# S4M13.net
KiCad netlist of a schematic drawn in EAGLE
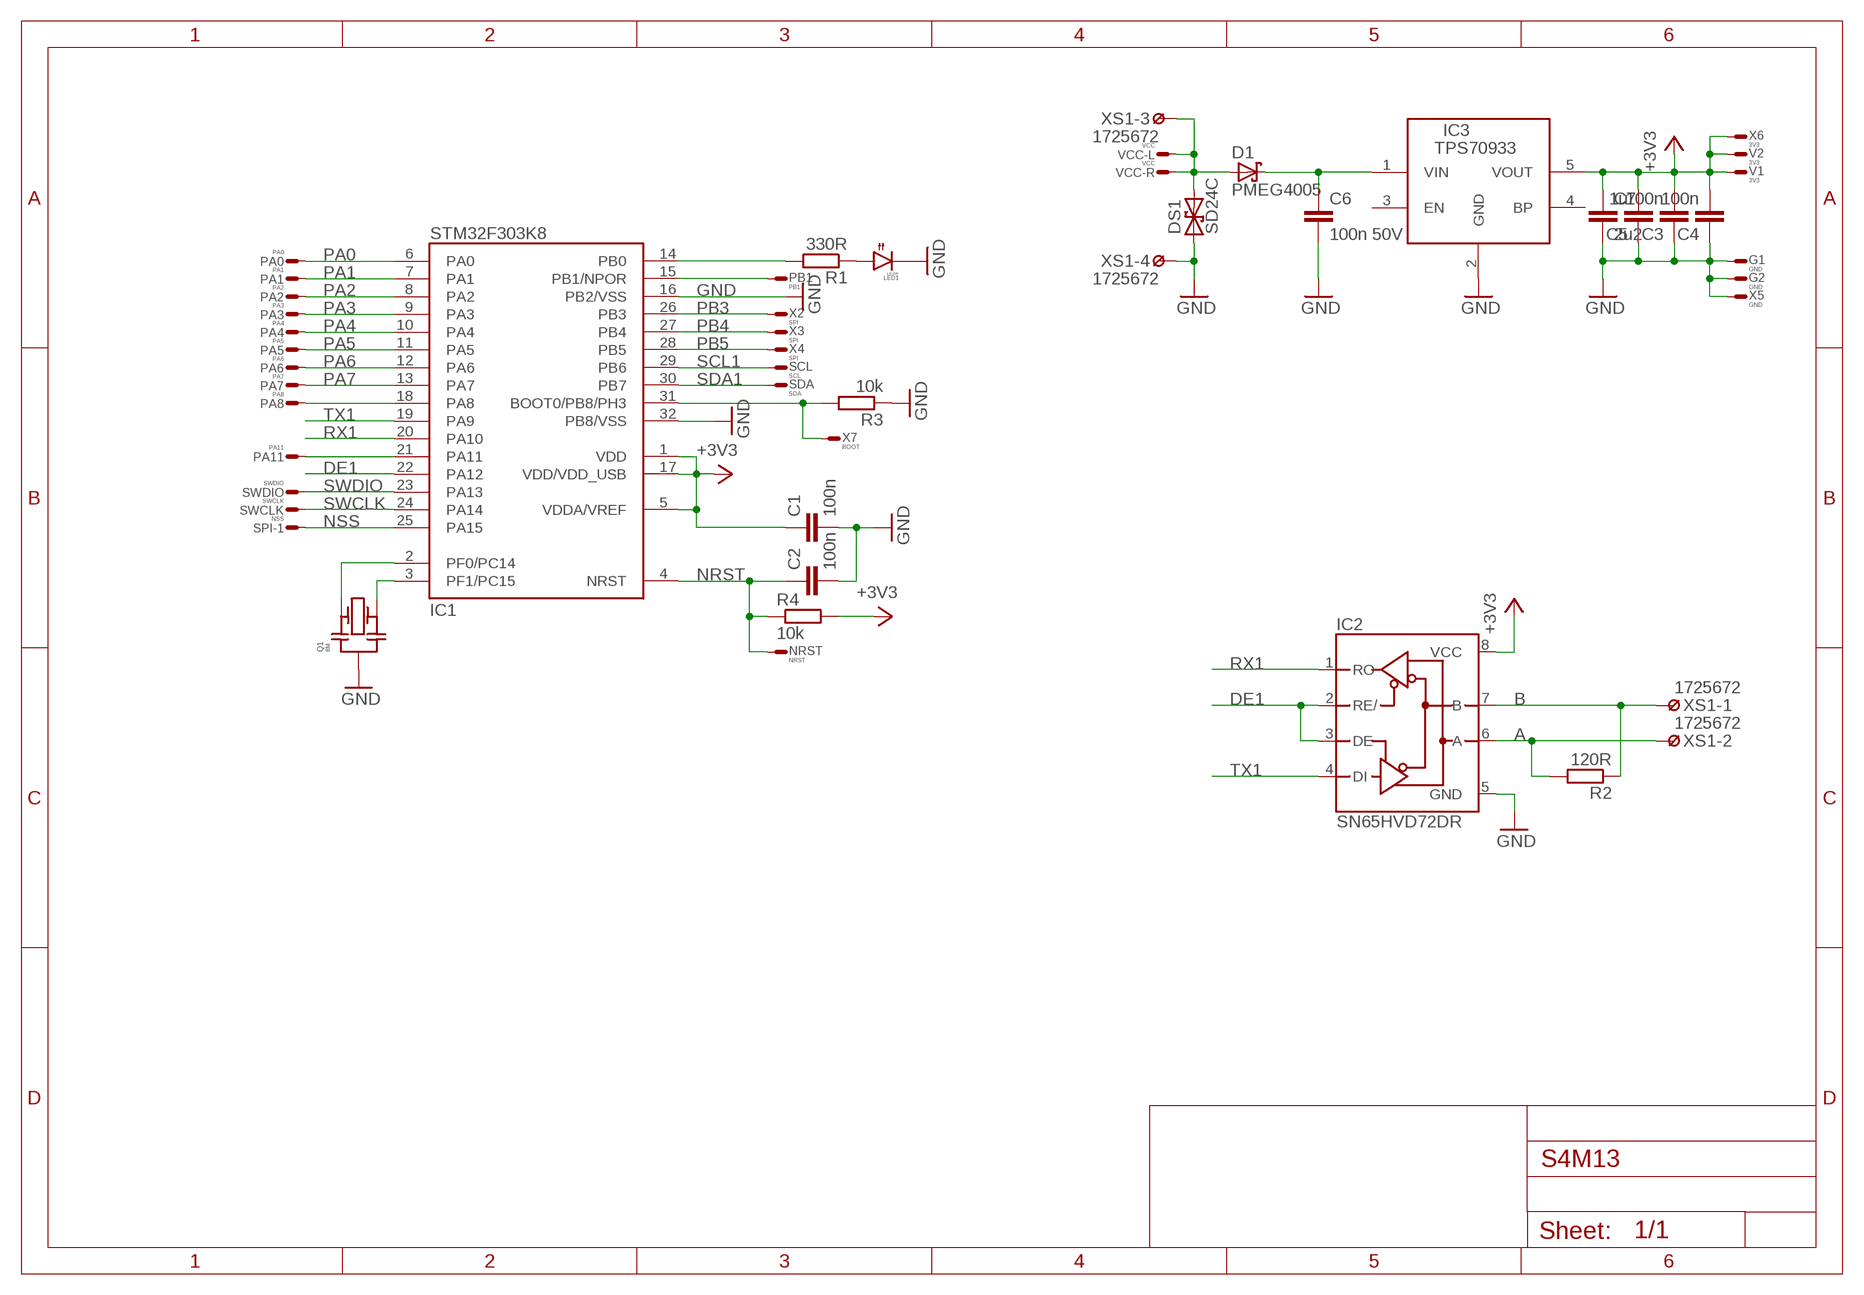
[diagram p0: schematic, sheet 1]

(export (version "E")
  (design (tool "Eeschema 10.0.6"))
  (components
    (comp (ref "C1")
      (value "100n")
      (footprint "eagle-import:0603")
      (libsource (lib "eagle-import") (part "C0603"))
    )
    (comp (ref "C2")
      (value "100n")
      (footprint "eagle-import:0603")
      (libsource (lib "eagle-import") (part "C0603"))
    )
    (comp (ref "C3")
      (value "100n")
      (footprint "eagle-import:0603")
      (libsource (lib "eagle-import") (part "C0603"))
    )
    (comp (ref "C4")
      (value "100n")
      (footprint "eagle-import:0603")
      (libsource (lib "eagle-import") (part "C0603"))
    )
    (comp (ref "C5")
      (value "1u")
      (footprint "eagle-import:0603")
      (libsource (lib "eagle-import") (part "C0603"))
    )
    (comp (ref "C6")
      (value "100n 50V")
      (footprint "eagle-import:0603")
      (libsource (lib "eagle-import") (part "C0603"))
    )
    (comp (ref "C7")
      (value "2u2")
      (footprint "eagle-import:0603")
      (libsource (lib "eagle-import") (part "C0603"))
    )
    (comp (ref "D1")
      (value "PMEG4005")
      (footprint "eagle-import:SOD323")
      (libsource (lib "eagle-import") (part "D-SCHOTKY323"))
    )
    (comp (ref "DS1")
      (value "SD24C")
      (footprint "eagle-import:SOD323")
      (libsource (lib "eagle-import") (part "TVS-U323"))
    )
    (comp (ref "G1")
      (value "GND")
      (footprint "eagle-import:T1.6_0.9")
      (libsource (lib "eagle-import") (part "WIREPADT1.6/0.9"))
    )
    (comp (ref "G2")
      (value "GND")
      (footprint "eagle-import:T1.6_0.9")
      (libsource (lib "eagle-import") (part "WIREPADT1.6/0.9"))
    )
    (comp (ref "IC1")
      (value "STM32F303K8")
      (footprint "eagle-import:LQFP32-7X7")
      (libsource (lib "eagle-import") (part "STM32_LQFP32"))
    )
    (comp (ref "IC2")
      (value "SN65HVD72DR")
      (footprint "eagle-import:SOIC8")
      (libsource (lib "eagle-import") (part "MAX485"))
    )
    (comp (ref "IC3")
      (value "TPS70933")
      (footprint "eagle-import:SOT23-5")
      (libsource (lib "eagle-import") (part "LDO"))
    )
    (comp (ref "LED1")
      (value "LEDR")
      (footprint "eagle-import:1206")
      (libsource (lib "eagle-import") (part "LED1206"))
    )
    (comp (ref "NRST")
      (value "NRST")
      (footprint "eagle-import:T1.6_0.9")
      (libsource (lib "eagle-import") (part "WIREPADT1.6/0.9"))
    )
    (comp (ref "PA0")
      (value "PA0")
      (footprint "eagle-import:T1.6_0.9")
      (libsource (lib "eagle-import") (part "WIREPADT1.6/0.9"))
    )
    (comp (ref "PA1")
      (value "PA1")
      (footprint "eagle-import:T1.6_0.9")
      (libsource (lib "eagle-import") (part "WIREPADT1.6/0.9"))
    )
    (comp (ref "PA2")
      (value "PA2")
      (footprint "eagle-import:T1.6_0.9")
      (libsource (lib "eagle-import") (part "WIREPADT1.6/0.9"))
    )
    (comp (ref "PA3")
      (value "PA3")
      (footprint "eagle-import:T1.6_0.9")
      (libsource (lib "eagle-import") (part "WIREPADT1.6/0.9"))
    )
    (comp (ref "PA4")
      (value "PA4")
      (footprint "eagle-import:T1.6_0.9")
      (libsource (lib "eagle-import") (part "WIREPADT1.6/0.9"))
    )
    (comp (ref "PA5")
      (value "PA5")
      (footprint "eagle-import:T1.6_0.9")
      (libsource (lib "eagle-import") (part "WIREPADT1.6/0.9"))
    )
    (comp (ref "PA6")
      (value "PA6")
      (footprint "eagle-import:T1.6_0.9")
      (libsource (lib "eagle-import") (part "WIREPADT1.6/0.9"))
    )
    (comp (ref "PA7")
      (value "PA7")
      (footprint "eagle-import:T1.6_0.9")
      (libsource (lib "eagle-import") (part "WIREPADT1.6/0.9"))
    )
    (comp (ref "PA8")
      (value "PA8")
      (footprint "eagle-import:T1.6_0.9")
      (libsource (lib "eagle-import") (part "WIREPADT1.6/0.9"))
    )
    (comp (ref "PA11")
      (value "PA11")
      (footprint "eagle-import:T1.6_0.9")
      (libsource (lib "eagle-import") (part "WIREPADT1.6/0.9"))
    )
    (comp (ref "PB1")
      (value "PB1")
      (footprint "eagle-import:T1.6_0.9")
      (libsource (lib "eagle-import") (part "WIREPADT1.6/0.9"))
    )
    (comp (ref "Q1")
      (value "8M")
      (footprint "eagle-import:CSTCE")
      (libsource (lib "eagle-import") (part "QRCE"))
    )
    (comp (ref "R1")
      (value "330R")
      (footprint "eagle-import:0603")
      (libsource (lib "eagle-import") (part "R0603"))
    )
    (comp (ref "R2")
      (value "120R")
      (footprint "eagle-import:0603")
      (libsource (lib "eagle-import") (part "R0603"))
    )
    (comp (ref "R3")
      (value "10k")
      (footprint "eagle-import:0603")
      (libsource (lib "eagle-import") (part "R0603"))
    )
    (comp (ref "R4")
      (value "10k")
      (footprint "eagle-import:0603")
      (libsource (lib "eagle-import") (part "R0603"))
    )
    (comp (ref "SCL")
      (value "SCL")
      (footprint "eagle-import:T1.6_0.9")
      (libsource (lib "eagle-import") (part "WIREPADT1.6/0.9"))
    )
    (comp (ref "SDA")
      (value "SDA")
      (footprint "eagle-import:T1.6_0.9")
      (libsource (lib "eagle-import") (part "WIREPADT1.6/0.9"))
    )
    (comp (ref "SPI-1")
      (value "NSS")
      (footprint "eagle-import:S1.6_0.8")
      (libsource (lib "eagle-import") (part "WIREPADS1.6/0.8"))
    )
    (comp (ref "SWCLK")
      (value "SWCLK")
      (footprint "eagle-import:T1.6_0.9")
      (libsource (lib "eagle-import") (part "WIREPADT1.6/0.9"))
    )
    (comp (ref "SWDIO")
      (value "SWDIO")
      (footprint "eagle-import:T1.6_0.9")
      (libsource (lib "eagle-import") (part "WIREPADT1.6/0.9"))
    )
    (comp (ref "V1")
      (value "3V3")
      (footprint "eagle-import:T1.6_0.9")
      (libsource (lib "eagle-import") (part "WIREPADT1.6/0.9"))
    )
    (comp (ref "V2")
      (value "3V3")
      (footprint "eagle-import:T1.6_0.9")
      (libsource (lib "eagle-import") (part "WIREPADT1.6/0.9"))
    )
    (comp (ref "VCC-L")
      (value "VCC")
      (footprint "eagle-import:T1.6_0.9")
      (libsource (lib "eagle-import") (part "WIREPADT1.6/0.9"))
    )
    (comp (ref "VCC-R")
      (value "VCC")
      (footprint "eagle-import:T1.6_0.9")
      (libsource (lib "eagle-import") (part "WIREPADT1.6/0.9"))
    )
    (comp (ref "X2")
      (value "SPI")
      (footprint "eagle-import:S1.6_0.8")
      (libsource (lib "eagle-import") (part "WIREPADS1.6/0.8"))
    )
    (comp (ref "X3")
      (value "SPI")
      (footprint "eagle-import:S1.6_0.8")
      (libsource (lib "eagle-import") (part "WIREPADS1.6/0.8"))
    )
    (comp (ref "X4")
      (value "SPI")
      (footprint "eagle-import:S1.6_0.8")
      (libsource (lib "eagle-import") (part "WIREPADS1.6/0.8"))
    )
    (comp (ref "X5")
      (value "GND")
      (footprint "eagle-import:S1.6_0.8")
      (libsource (lib "eagle-import") (part "WIREPADS1.6/0.8"))
    )
    (comp (ref "X6")
      (value "3V3")
      (footprint "eagle-import:S1.6_0.8")
      (libsource (lib "eagle-import") (part "WIREPADS1.6/0.8"))
    )
    (comp (ref "X7")
      (value "BOOT")
      (footprint "eagle-import:S1.27R")
      (libsource (lib "eagle-import") (part "WIREPADR"))
    )
    (comp (ref "XS1")
      (value "1725672")
      (footprint "eagle-import:1725672")
      (libsource (lib "eagle-import") (part "1725672"))
    )
  )
  (nets
    (net (code "1") (name "+3V3") (class "Default")
      (node (ref "C1") (pin "1") (pinfunction "1_1") (pintype "passive"))
      (node (ref "C3") (pin "2") (pinfunction "2_2") (pintype "passive"))
      (node (ref "C4") (pin "2") (pinfunction "2_2") (pintype "passive"))
      (node (ref "C5") (pin "2") (pinfunction "2_2") (pintype "passive"))
      (node (ref "C7") (pin "1") (pinfunction "1_1") (pintype "passive"))
      (node (ref "IC1") (pin "1") (pinfunction "VDD_1") (pintype "bidirectional"))
      (node (ref "IC1") (pin "17") (pinfunction "VDD/VDD_USB_17") (pintype "bidirectional"))
      (node (ref "IC1") (pin "5") (pinfunction "VDDA/VREF_5") (pintype "bidirectional"))
      (node (ref "IC2") (pin "8") (pinfunction "VCC_8") (pintype "bidirectional"))
      (node (ref "IC3") (pin "5") (pinfunction "VOUT_5") (pintype "bidirectional"))
      (node (ref "R4") (pin "2") (pinfunction "2_2") (pintype "passive"))
      (node (ref "V1") (pin "1") (pinfunction "S_1") (pintype "passive"))
      (node (ref "V2") (pin "1") (pinfunction "S_1") (pintype "passive"))
      (node (ref "X6") (pin "W") (pinfunction "S_W") (pintype "passive"))
    )
    (net (code "2") (name "/A") (class "Default")
      (node (ref "IC2") (pin "6") (pinfunction "A_6") (pintype "bidirectional"))
      (node (ref "R2") (pin "2") (pinfunction "2_2") (pintype "passive"))
      (node (ref "XS1") (pin "2") (pinfunction "K_2") (pintype "passive"))
    )
    (net (code "3") (name "/B") (class "Default")
      (node (ref "IC2") (pin "7") (pinfunction "B_7") (pintype "bidirectional"))
      (node (ref "R2") (pin "1") (pinfunction "1_1") (pintype "passive"))
      (node (ref "XS1") (pin "1") (pinfunction "K_1") (pintype "passive"))
    )
    (net (code "4") (name "/DE1") (class "Default")
      (node (ref "IC1") (pin "22") (pinfunction "PA12_22") (pintype "bidirectional"))
      (node (ref "IC2") (pin "2") (pinfunction "RE/_2") (pintype "bidirectional"))
      (node (ref "IC2") (pin "3") (pinfunction "DE_3") (pintype "bidirectional"))
    )
    (net (code "5") (name "/NRST") (class "Default")
      (node (ref "C2") (pin "1") (pinfunction "1_1") (pintype "passive"))
      (node (ref "IC1") (pin "4") (pinfunction "NRST_4") (pintype "bidirectional"))
      (node (ref "NRST") (pin "1") (pinfunction "S_1") (pintype "passive"))
      (node (ref "R4") (pin "1") (pinfunction "1_1") (pintype "passive"))
    )
    (net (code "6") (name "/NSS") (class "Default")
      (node (ref "IC1") (pin "25") (pinfunction "PA15_25") (pintype "bidirectional"))
      (node (ref "SPI-1") (pin "W") (pinfunction "S_W") (pintype "passive"))
    )
    (net (code "7") (name "/PA0") (class "Default")
      (node (ref "IC1") (pin "6") (pinfunction "PA0_6") (pintype "bidirectional"))
      (node (ref "PA0") (pin "1") (pinfunction "S_1") (pintype "passive"))
    )
    (net (code "8") (name "/PA1") (class "Default")
      (node (ref "IC1") (pin "7") (pinfunction "PA1_7") (pintype "bidirectional"))
      (node (ref "PA1") (pin "1") (pinfunction "S_1") (pintype "passive"))
    )
    (net (code "9") (name "/PA2") (class "Default")
      (node (ref "IC1") (pin "8") (pinfunction "PA2_8") (pintype "bidirectional"))
      (node (ref "PA2") (pin "1") (pinfunction "S_1") (pintype "passive"))
    )
    (net (code "10") (name "/PA3") (class "Default")
      (node (ref "IC1") (pin "9") (pinfunction "PA3_9") (pintype "bidirectional"))
      (node (ref "PA3") (pin "1") (pinfunction "S_1") (pintype "passive"))
    )
    (net (code "11") (name "/PA4") (class "Default")
      (node (ref "IC1") (pin "10") (pinfunction "PA4_10") (pintype "bidirectional"))
      (node (ref "PA4") (pin "1") (pinfunction "S_1") (pintype "passive"))
    )
    (net (code "12") (name "/PA5") (class "Default")
      (node (ref "IC1") (pin "11") (pinfunction "PA5_11") (pintype "bidirectional"))
      (node (ref "PA5") (pin "1") (pinfunction "S_1") (pintype "passive"))
    )
    (net (code "13") (name "/PA6") (class "Default")
      (node (ref "IC1") (pin "12") (pinfunction "PA6_12") (pintype "bidirectional"))
      (node (ref "PA6") (pin "1") (pinfunction "S_1") (pintype "passive"))
    )
    (net (code "14") (name "/PA7") (class "Default")
      (node (ref "IC1") (pin "13") (pinfunction "PA7_13") (pintype "bidirectional"))
      (node (ref "PA7") (pin "1") (pinfunction "S_1") (pintype "passive"))
    )
    (net (code "15") (name "/PB3") (class "Default")
      (node (ref "IC1") (pin "26") (pinfunction "PB3_26") (pintype "bidirectional"))
      (node (ref "X2") (pin "W") (pinfunction "S_W") (pintype "passive"))
    )
    (net (code "16") (name "/PB4") (class "Default")
      (node (ref "IC1") (pin "27") (pinfunction "PB4_27") (pintype "bidirectional"))
      (node (ref "X3") (pin "W") (pinfunction "S_W") (pintype "passive"))
    )
    (net (code "17") (name "/PB5") (class "Default")
      (node (ref "IC1") (pin "28") (pinfunction "PB5_28") (pintype "bidirectional"))
      (node (ref "X4") (pin "W") (pinfunction "S_W") (pintype "passive"))
    )
    (net (code "18") (name "/RX1") (class "Default")
      (node (ref "IC1") (pin "20") (pinfunction "PA10_20") (pintype "bidirectional"))
      (node (ref "IC2") (pin "1") (pinfunction "RO_1") (pintype "bidirectional"))
    )
    (net (code "19") (name "/SCL1") (class "Default")
      (node (ref "IC1") (pin "29") (pinfunction "PB6_29") (pintype "bidirectional"))
      (node (ref "SCL") (pin "1") (pinfunction "S_1") (pintype "passive"))
    )
    (net (code "20") (name "/SDA1") (class "Default")
      (node (ref "IC1") (pin "30") (pinfunction "PB7_30") (pintype "bidirectional"))
      (node (ref "SDA") (pin "1") (pinfunction "S_1") (pintype "passive"))
    )
    (net (code "21") (name "/SWCLK") (class "Default")
      (node (ref "IC1") (pin "24") (pinfunction "PA14_24") (pintype "bidirectional"))
      (node (ref "SWCLK") (pin "1") (pinfunction "S_1") (pintype "passive"))
    )
    (net (code "22") (name "/SWDIO") (class "Default")
      (node (ref "IC1") (pin "23") (pinfunction "PA13_23") (pintype "bidirectional"))
      (node (ref "SWDIO") (pin "1") (pinfunction "S_1") (pintype "passive"))
    )
    (net (code "23") (name "/TX1") (class "Default")
      (node (ref "IC1") (pin "19") (pinfunction "PA9_19") (pintype "bidirectional"))
      (node (ref "IC2") (pin "4") (pinfunction "DI_4") (pintype "bidirectional"))
    )
    (net (code "24") (name "GND") (class "Default")
      (node (ref "C1") (pin "2") (pinfunction "2_2") (pintype "passive"))
      (node (ref "C2") (pin "2") (pinfunction "2_2") (pintype "passive"))
      (node (ref "C3") (pin "1") (pinfunction "1_1") (pintype "passive"))
      (node (ref "C4") (pin "1") (pinfunction "1_1") (pintype "passive"))
      (node (ref "C5") (pin "1") (pinfunction "1_1") (pintype "passive"))
      (node (ref "C6") (pin "2") (pinfunction "2_2") (pintype "passive"))
      (node (ref "C7") (pin "2") (pinfunction "2_2") (pintype "passive"))
      (node (ref "DS1") (pin "A") (pinfunction "1_A") (pintype "passive"))
      (node (ref "G1") (pin "1") (pinfunction "S_1") (pintype "passive"))
      (node (ref "G2") (pin "1") (pinfunction "S_1") (pintype "passive"))
      (node (ref "IC1") (pin "16") (pinfunction "PB2/VSS_16") (pintype "bidirectional"))
      (node (ref "IC1") (pin "32") (pinfunction "PB8/VSS_32") (pintype "bidirectional"))
      (node (ref "IC2") (pin "5") (pinfunction "GND_5") (pintype "bidirectional"))
      (node (ref "IC3") (pin "2") (pinfunction "GND_2") (pintype "bidirectional"))
      (node (ref "LED1") (pin "2") (pinfunction "C_2") (pintype "bidirectional"))
      (node (ref "Q1") (pin "G") (pinfunction "M_G") (pintype "passive"))
      (node (ref "R3") (pin "1") (pinfunction "1_1") (pintype "passive"))
      (node (ref "X5") (pin "W") (pinfunction "S_W") (pintype "passive"))
      (node (ref "XS1") (pin "4") (pinfunction "K_4") (pintype "passive"))
    )
    (net (code "25") (name "Net-(DS1-2)") (class "Default")
      (node (ref "D1") (pin "A") (pinfunction "A_A") (pintype "passive"))
      (node (ref "DS1") (pin "C") (pinfunction "2_C") (pintype "passive"))
      (node (ref "VCC-L") (pin "1") (pinfunction "S_1") (pintype "passive"))
      (node (ref "VCC-R") (pin "1") (pinfunction "S_1") (pintype "passive"))
      (node (ref "XS1") (pin "3") (pinfunction "K_3") (pintype "passive"))
    )
    (net (code "26") (name "Net-(IC1-BOOT0{slash}PB8{slash}PH3)") (class "Default")
      (node (ref "IC1") (pin "31") (pinfunction "BOOT0/PB8/PH3_31") (pintype "bidirectional"))
      (node (ref "R3") (pin "2") (pinfunction "2_2") (pintype "passive"))
      (node (ref "X7") (pin "1") (pinfunction "S_1") (pintype "passive"))
    )
    (net (code "27") (name "Net-(IC1-PA8)") (class "Default")
      (node (ref "IC1") (pin "18") (pinfunction "PA8_18") (pintype "bidirectional"))
      (node (ref "PA8") (pin "1") (pinfunction "S_1") (pintype "passive"))
    )
    (net (code "28") (name "Net-(IC1-PA11)") (class "Default")
      (node (ref "IC1") (pin "21") (pinfunction "PA11_21") (pintype "bidirectional"))
      (node (ref "PA11") (pin "1") (pinfunction "S_1") (pintype "passive"))
    )
    (net (code "29") (name "Net-(IC1-PB0)") (class "Default")
      (node (ref "IC1") (pin "14") (pinfunction "PB0_14") (pintype "bidirectional"))
      (node (ref "R1") (pin "2") (pinfunction "2_2") (pintype "passive"))
    )
    (net (code "30") (name "Net-(IC1-PB1{slash}NPOR)") (class "Default")
      (node (ref "IC1") (pin "15") (pinfunction "PB1/NPOR_15") (pintype "bidirectional"))
      (node (ref "PB1") (pin "1") (pinfunction "S_1") (pintype "passive"))
    )
    (net (code "31") (name "Net-(IC1-PF0{slash}PC14)") (class "Default")
      (node (ref "IC1") (pin "2") (pinfunction "PF0/PC14_2") (pintype "bidirectional"))
      (node (ref "Q1") (pin "A") (pinfunction "1_A") (pintype "passive"))
    )
    (net (code "32") (name "Net-(IC1-PF1{slash}PC15)") (class "Default")
      (node (ref "IC1") (pin "3") (pinfunction "PF1/PC15_3") (pintype "bidirectional"))
      (node (ref "Q1") (pin "B") (pinfunction "2_B") (pintype "passive"))
    )
    (net (code "33") (name "Net-(IC3-VIN)") (class "Default")
      (node (ref "C6") (pin "1") (pinfunction "1_1") (pintype "passive"))
      (node (ref "D1") (pin "C") (pinfunction "C_C") (pintype "passive"))
      (node (ref "IC3") (pin "1") (pinfunction "VIN_1") (pintype "bidirectional"))
    )
    (net (code "34") (name "Net-(LED1-A)") (class "Default")
      (node (ref "LED1") (pin "1") (pinfunction "A_1") (pintype "bidirectional"))
      (node (ref "R1") (pin "1") (pinfunction "1_1") (pintype "passive"))
    )
    (net (code "35") (name "unconnected-(IC3-BP-Pad4)") (class "Default")
      (node (ref "IC3") (pin "4") (pinfunction "BP_4") (pintype "bidirectional"))
    )
    (net (code "36") (name "unconnected-(IC3-EN-Pad3)") (class "Default")
      (node (ref "IC3") (pin "3") (pinfunction "EN_3") (pintype "bidirectional"))
    )
  )
)
